# power.net
KiCad netlist of a schematic drawn in Altium Designer
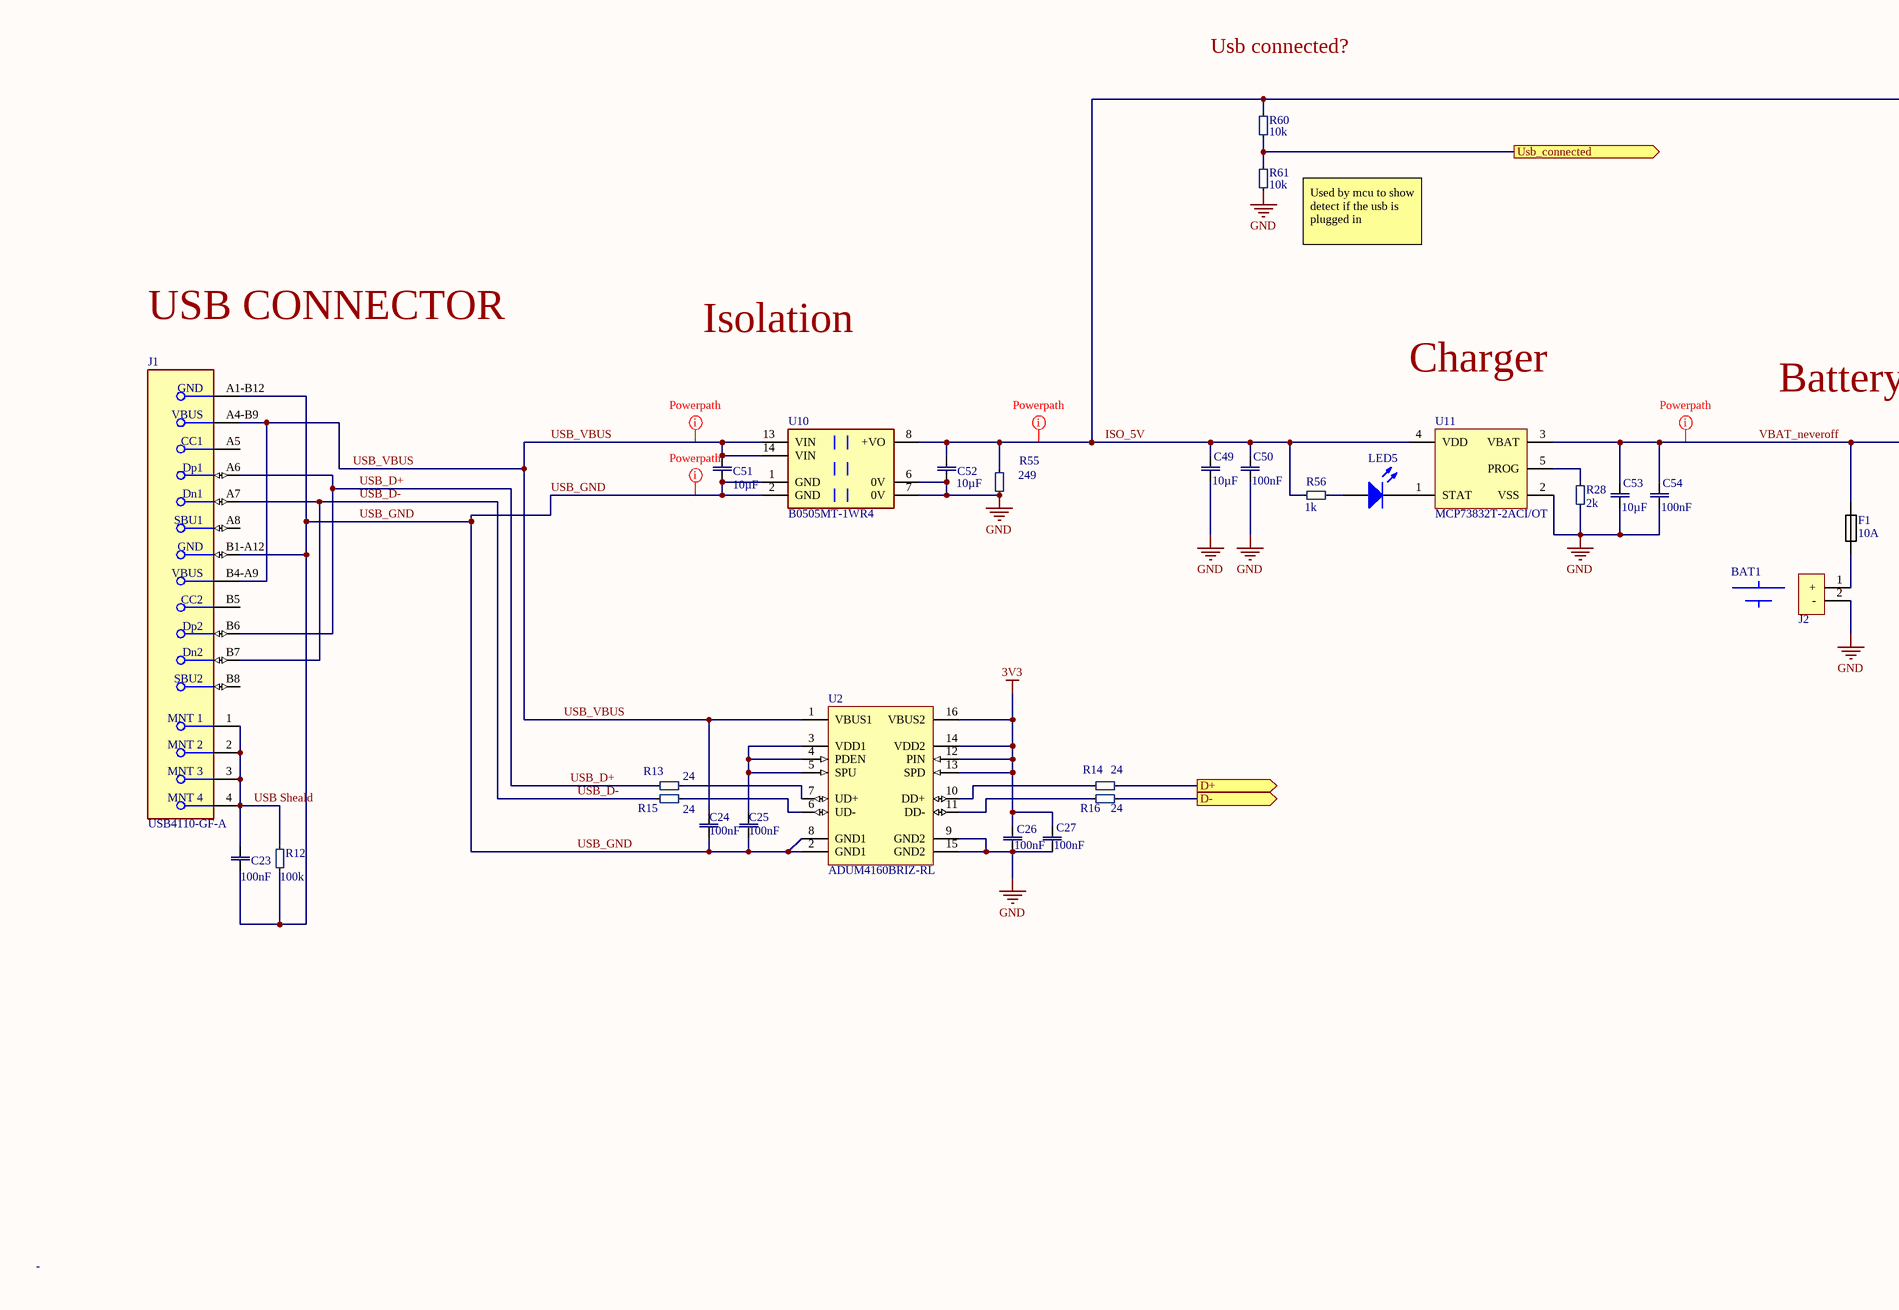
[diagram p0: power.SchDoc, left]
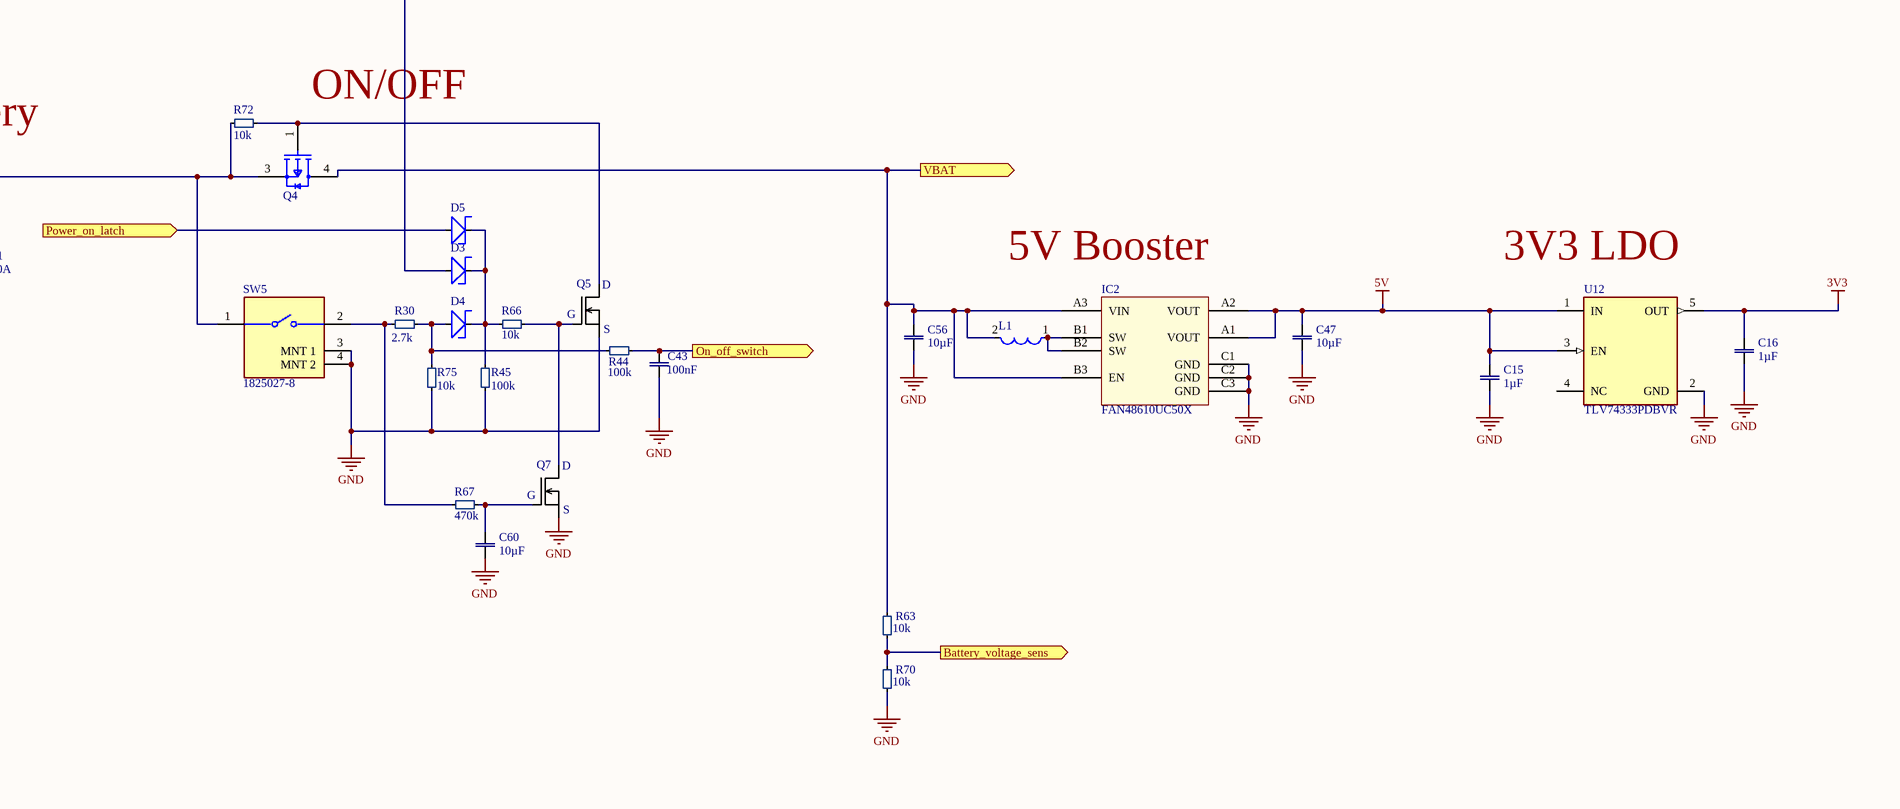
[diagram p1: power.SchDoc, right]

(export (version "E")
  (design (tool "Eeschema 10.0.6"))
  (components
    (comp (ref "BAT1")
      (value "THN803465AJ")
      (footprint "THN803465AJ-Footprint-1")
      (description "2500mAh 3.7V 1S 25C LiPO Battery JST plug for Drone RC Model Airplane Helicopter")
      (fields (field (name "VOLTAGE") "3.7V"))
      (libsource (lib "concord server") (part "battery"))
    )
    (comp (ref "C15")
      (value "CL21B105KBFNNNG")
      (footprint "CAP0805")
      (description "SAMSUNG ELECTRO-MECHANICS - CL21B105KBFNNNG - MLCC CAPACITORS")
      (fields
        (field (name "VOLTAGE") "50V")
        (field (name "CAPACITANCE") "1µF")
        (field (name "TOLERANCE") "10%")
      )
      (libsource (lib "concord server") (part "Capasitor_keramic_generic"))
    )
    (comp (ref "C16")
      (value "CL21B105KBFNNNG")
      (footprint "CAP0805")
      (description "SAMSUNG ELECTRO-MECHANICS - CL21B105KBFNNNG - MLCC CAPACITORS")
      (fields
        (field (name "VOLTAGE") "50V")
        (field (name "CAPACITANCE") "1µF")
        (field (name "TOLERANCE") "10%")
      )
      (libsource (lib "concord server") (part "Capasitor_keramic_generic"))
    )
    (comp (ref "C23")
      (value "GRM155R71H104ME14D")
      (footprint "cap0402")
      (description "0402 0.1 uF 50 V ±20% Tolerance X7R SMT Monolithic Ceramic Chip Capacitor")
      (fields
        (field (name "CAPACITANCE") "100nF")
        (field (name "TOLERANCE") "20%")
        (field (name "LCSC PART#") "C182412")
      )
      (libsource (lib "concord server") (part "Capasitor_keramic_generic"))
    )
    (comp (ref "C24")
      (value "GRM155R71H104ME14D")
      (footprint "cap0402")
      (description "0402 0.1 uF 50 V ±20% Tolerance X7R SMT Monolithic Ceramic Chip Capacitor")
      (fields
        (field (name "CAPACITANCE") "100nF")
        (field (name "TOLERANCE") "20%")
        (field (name "LCSC PART#") "C182412")
      )
      (libsource (lib "concord server") (part "Capasitor_keramic_generic"))
    )
    (comp (ref "C25")
      (value "GRM155R71H104ME14D")
      (footprint "cap0402")
      (description "0402 0.1 uF 50 V ±20% Tolerance X7R SMT Monolithic Ceramic Chip Capacitor")
      (fields
        (field (name "CAPACITANCE") "100nF")
        (field (name "TOLERANCE") "20%")
        (field (name "LCSC PART#") "C182412")
      )
      (libsource (lib "concord server") (part "Capasitor_keramic_generic"))
    )
    (comp (ref "C26")
      (value "GRM155R71H104ME14D")
      (footprint "cap0402")
      (description "0402 0.1 uF 50 V ±20% Tolerance X7R SMT Monolithic Ceramic Chip Capacitor")
      (fields
        (field (name "CAPACITANCE") "100nF")
        (field (name "TOLERANCE") "20%")
        (field (name "LCSC PART#") "C182412")
      )
      (libsource (lib "concord server") (part "Capasitor_keramic_generic"))
    )
    (comp (ref "C27")
      (value "GRM155R71H104ME14D")
      (footprint "cap0402")
      (description "0402 0.1 uF 50 V ±20% Tolerance X7R SMT Monolithic Ceramic Chip Capacitor")
      (fields
        (field (name "CAPACITANCE") "100nF")
        (field (name "TOLERANCE") "20%")
        (field (name "LCSC PART#") "C182412")
      )
      (libsource (lib "concord server") (part "Capasitor_keramic_generic"))
    )
    (comp (ref "C43")
      (value "GRM155R71H104ME14D")
      (footprint "cap0402")
      (description "0402 0.1 uF 50 V ±20% Tolerance X7R SMT Monolithic Ceramic Chip Capacitor")
      (fields
        (field (name "CAPACITANCE") "100nF")
        (field (name "TOLERANCE") "20%")
        (field (name "LCSC PART#") "C182412")
      )
      (libsource (lib "concord server") (part "Capasitor_keramic_generic"))
    )
    (comp (ref "C47")
      (value "CL31A106MBHNNNE")
      (footprint "Chip2PinSM127P600-8N")
      (description "CAP CER 10UF 50V X5R 1206")
      (fields
        (field (name "CAPACITANCE") "10µF")
        (field (name "TOLERANCE") "20%")
        (field (name "LCSC PART#") "C96600")
      )
      (libsource (lib "concord server") (part "Capasitor_keramic_generic"))
    )
    (comp (ref "C49")
      (value "CL31A106MBHNNNE")
      (footprint "Chip2PinSM127P600-8N")
      (description "CAP CER 10UF 50V X5R 1206")
      (fields
        (field (name "CAPACITANCE") "10µF")
        (field (name "TOLERANCE") "20%")
        (field (name "LCSC PART#") "C96600")
      )
      (libsource (lib "concord server") (part "Capasitor_keramic_generic"))
    )
    (comp (ref "C50")
      (value "GRM155R71H104ME14D")
      (footprint "cap0402")
      (description "0402 0.1 uF 50 V ±20% Tolerance X7R SMT Monolithic Ceramic Chip Capacitor")
      (fields
        (field (name "CAPACITANCE") "100nF")
        (field (name "TOLERANCE") "20%")
        (field (name "LCSC PART#") "C182412")
      )
      (libsource (lib "concord server") (part "Capasitor_keramic_generic"))
    )
    (comp (ref "C51")
      (value "CL31A106MBHNNNE")
      (footprint "Chip2PinSM127P600-8N")
      (description "CAP CER 10UF 50V X5R 1206")
      (fields
        (field (name "CAPACITANCE") "10µF")
        (field (name "TOLERANCE") "20%")
        (field (name "LCSC PART#") "C96600")
      )
      (libsource (lib "concord server") (part "Capasitor_keramic_generic"))
    )
    (comp (ref "C52")
      (value "CL31A106MBHNNNE")
      (footprint "Chip2PinSM127P600-8N")
      (description "CAP CER 10UF 50V X5R 1206")
      (fields
        (field (name "CAPACITANCE") "10µF")
        (field (name "TOLERANCE") "20%")
        (field (name "LCSC PART#") "C96600")
      )
      (libsource (lib "concord server") (part "Capasitor_keramic_generic"))
    )
    (comp (ref "C53")
      (value "CL31A106MBHNNNE")
      (footprint "Chip2PinSM127P600-8N")
      (description "CAP CER 10UF 50V X5R 1206")
      (fields
        (field (name "CAPACITANCE") "10µF")
        (field (name "TOLERANCE") "20%")
        (field (name "LCSC PART#") "C96600")
      )
      (libsource (lib "concord server") (part "Capasitor_keramic_generic"))
    )
    (comp (ref "C54")
      (value "GRM155R71H104ME14D")
      (footprint "cap0402")
      (description "0402 0.1 uF 50 V ±20% Tolerance X7R SMT Monolithic Ceramic Chip Capacitor")
      (fields
        (field (name "CAPACITANCE") "100nF")
        (field (name "TOLERANCE") "20%")
        (field (name "LCSC PART#") "C182412")
      )
      (libsource (lib "concord server") (part "Capasitor_keramic_generic"))
    )
    (comp (ref "C56")
      (value "CL31A106MBHNNNE")
      (footprint "Chip2PinSM127P600-8N")
      (description "CAP CER 10UF 50V X5R 1206")
      (fields
        (field (name "CAPACITANCE") "10µF")
        (field (name "TOLERANCE") "20%")
        (field (name "LCSC PART#") "C96600")
      )
      (libsource (lib "concord server") (part "Capasitor_keramic_generic"))
    )
    (comp (ref "C60")
      (value "CL31A106MBHNNNE")
      (footprint "Chip2PinSM127P600-8N")
      (description "CAP CER 10UF 50V X5R 1206")
      (fields
        (field (name "CAPACITANCE") "10µF")
        (field (name "TOLERANCE") "20%")
        (field (name "LCSC PART#") "C96600")
      )
      (libsource (lib "concord server") (part "Capasitor_keramic_generic"))
    )
    (comp (ref "D3")
      (value "BAS70_R1_00001")
      (footprint "SOT95P245X110-3N")
      (description "Diode Schottky 70 V 200mA Surface Mount SOT-23")
      (libsource (lib "concord server") (part "Schootkey diode"))
    )
    (comp (ref "D4")
      (value "BAS70_R1_00001")
      (footprint "SOT95P245X110-3N")
      (description "Diode Schottky 70 V 200mA Surface Mount SOT-23")
      (libsource (lib "concord server") (part "Schootkey diode"))
    )
    (comp (ref "D5")
      (value "BAS70_R1_00001")
      (footprint "SOT95P245X110-3N")
      (description "Diode Schottky 70 V 200mA Surface Mount SOT-23")
      (libsource (lib "concord server") (part "Schootkey diode"))
    )
    (comp (ref "F1")
      (value "0685H9100-01")
      (footprint "RESC3216X06N")
      (description "Fuse Chip Fast Acting 10A 125V SMD Solder Pad 1206 3.2 X 1.58 X 0.65mm Ceramic T/R Automotive")
      (fields (field (name "CURRENT RATING") "10A"))
      (libsource (lib "concord server") (part "0685H9100-01-Symbol-1"))
    )
    (comp (ref "IC2")
      (value "FAN48610UC50X")
      (footprint "BGA9C40P3X3_211X211X58")
      (description "2.5 MHz, 1 A, Fixed-Output Synchronous TinyBoost® Regulator")
      (fields (field (name "LCSC PART#") "C890712"))
      (libsource (lib "concord server") (part "FAN48610UC50X-Symbol-1"))
    )
    (comp (ref "J1")
      (value "USB4110-GF-A")
      (footprint "FP-USB4110-GF-A-MFG")
      (description "Conn Usb 2.0 Type-c R/a SMT")
      (libsource (lib "concord server") (part "e23f2b38bb3c3f98e683ebab9ede730"))
    )
    (comp (ref "J2")
      (value "1744048-2")
      (footprint "New footprint 1")
      (description "Conn Power HDR 2 POS 5.08mm Solder RA Thru-Hole 2 Terminal 1 Port Bag")
      (fields (field (name "LCSC PART#") "C590637"))
      (libsource (lib "concord server") (part "BU-P6883"))
    )
    (comp (ref "L1")
      (value "LQM21PNR47MC0D")
      (footprint "FP-LQM21PN_C0-IPC_C")
      (description "Inductor Power Chip Shielded Multi-Layer 0.47uH 20% 1MHz Ferrite 1.1A 0.15Ohm DCR 0805 T/R")
      (fields (field (name "LCSC PART#") "C341670"))
      (libsource (lib "concord server") (part "725321dda6339637d4d059423bc1c3c"))
    )
    (comp (ref "LED5")
      (value "150080BS75000")
      (footprint "0805_A")
      (description "SMD LED blue 3.5 V 0805, 150080BS75000, Würth Elektronik")
      (libsource (lib "concord server") (part "WE-LED_K1A2-2"))
    )
    (comp (ref "Q4")
      (value "RQ3C150BCTB")
      (footprint "RQ3C150BCTB-Footprint-1")
      (description "Trans Mosfet P-ch 20V 15A 8-PIN Hsmt Ep T/r")
      (fields (field (name "LCSC PART#") "C266247"))
      (libsource (lib "concord server") (part "pmos"))
    )
    (comp (ref "Q5")
      (value "SSM3K7002CFU,LF")
      (footprint "SSM3K7002CFU,LF-Footprint-1")
      (description "Trans MOSFET N-CH Si 60V 0.17A 3-Pin USM T/R")
      (fields (field (name "LCSC PART#") "C396059"))
      (libsource (lib "concord server") (part "nmos"))
    )
    (comp (ref "Q7")
      (value "SSM3K7002CFU,LF")
      (footprint "SSM3K7002CFU,LF-Footprint-1")
      (description "Trans MOSFET N-CH Si 60V 0.17A 3-Pin USM T/R")
      (fields (field (name "LCSC PART#") "C396059"))
      (libsource (lib "concord server") (part "nmos"))
    )
    (comp (ref "R12")
      (value "RC0402FR-07100KL")
      (footprint "SMD_0402(1005)_M")
      (description "Res General Purpose Thick Film 0402 100K Ohm 1% 1/16W ±100ppm/°C Molded SMD Paper T/R")
      (fields
        (field (name "RESISTANCE") "100k")
        (field (name "TOLERANCE") "1%")
        (field (name "LCSC PART#") "C60491")
      )
      (libsource (lib "concord server") (part "resistor_european"))
    )
    (comp (ref "R13")
      (value "RC0402FR-0724RL")
      (footprint "RESC0402(1005)_N")
      (description "Thick Film Resistors 24 OHM 1%")
      (fields
        (field (name "RESISTANCE") "24")
        (field (name "TOLERANCE") "1%")
        (field (name "LCSC PART#") "C274890")
      )
      (libsource (lib "concord server") (part "resistor_european"))
    )
    (comp (ref "R14")
      (value "RC0402FR-0724RL")
      (footprint "RESC0402(1005)_N")
      (description "Thick Film Resistors 24 OHM 1%")
      (fields
        (field (name "RESISTANCE") "24")
        (field (name "TOLERANCE") "1%")
        (field (name "LCSC PART#") "C274890")
      )
      (libsource (lib "concord server") (part "resistor_european"))
    )
    (comp (ref "R15")
      (value "RC0402FR-0724RL")
      (footprint "RESC0402(1005)_N")
      (description "Thick Film Resistors 24 OHM 1%")
      (fields
        (field (name "RESISTANCE") "24")
        (field (name "TOLERANCE") "1%")
        (field (name "LCSC PART#") "C274890")
      )
      (libsource (lib "concord server") (part "resistor_european"))
    )
    (comp (ref "R16")
      (value "RC0402FR-0724RL")
      (footprint "RESC0402(1005)_N")
      (description "Thick Film Resistors 24 OHM 1%")
      (fields
        (field (name "RESISTANCE") "24")
        (field (name "TOLERANCE") "1%")
        (field (name "LCSC PART#") "C274890")
      )
      (libsource (lib "concord server") (part "resistor_european"))
    )
    (comp (ref "R28")
      (value "RC0402FR-072KL")
      (footprint "RESC1005X40X25NL05T10")
      (description "Res General Purpose Thick Film 0402 2K Ohm 1% 1/16W ±100ppm/°C Molded SMD Paper T/R")
      (fields
        (field (name "RESISTANCE") "2k")
        (field (name "TOLERANCE") "1%")
        (field (name "LCSC PART#") "C138017")
      )
      (libsource (lib "concord server") (part "resistor_european"))
    )
    (comp (ref "R30")
      (value "RC0402FR-072K7L")
      (footprint "RESC1005X40X25NL05T10")
      (description "Res General Purpose Thick Film 0402 2.7k Ohm 1% 1/16W ±100ppm/°C Molded Paper T/R")
      (fields
        (field (name "RESISTANCE") "2.7k")
        (field (name "TOLERANCE") "1%")
        (field (name "LCSC PART#") "C138017")
      )
      (libsource (lib "concord server") (part "resistor_european"))
    )
    (comp (ref "R44")
      (value "RC0402FR-07100KL")
      (footprint "SMD_0402(1005)_M")
      (description "Res General Purpose Thick Film 0402 100K Ohm 1% 1/16W ±100ppm/°C Molded SMD Paper T/R")
      (fields
        (field (name "RESISTANCE") "100k")
        (field (name "TOLERANCE") "1%")
        (field (name "LCSC PART#") "C60491")
      )
      (libsource (lib "concord server") (part "resistor_european"))
    )
    (comp (ref "R45")
      (value "RC0402FR-07100KL")
      (footprint "SMD_0402(1005)_M")
      (description "Res General Purpose Thick Film 0402 100K Ohm 1% 1/16W ±100ppm/°C Molded SMD Paper T/R")
      (fields
        (field (name "RESISTANCE") "100k")
        (field (name "TOLERANCE") "1%")
        (field (name "LCSC PART#") "C60491")
      )
      (libsource (lib "concord server") (part "resistor_european"))
    )
    (comp (ref "R55")
      (value "RC0402FR-07249RL")
      (footprint "SMD_0402(1005)_M")
      (description "Res Thick Film 0402 249 Ohm 1% 1/16W ±100ppm/°C Molded SMD Paper T/R")
      (fields
        (field (name "RESISTANCE") "249")
        (field (name "TOLERANCE") "1%")
        (field (name "LCSC PART#") "C185439")
      )
      (libsource (lib "concord server") (part "resistor_european"))
    )
    (comp (ref "R56")
      (value "RC0402FR-071KL")
      (footprint "SMD_0402(1005)_M")
      (description "Surface Mount Chip Resistor, Thick Film, RC Series, 1 kohm, 62.5 mW, 1%, 50 V, 0402 [1005 Metric]")
      (fields
        (field (name "RESISTANCE") "1k")
        (field (name "TOLERANCE") "1%")
        (field (name "LCSC PART#") "C2935237")
      )
      (libsource (lib "concord server") (part "resistor_european"))
    )
    (comp (ref "R60")
      (value "RC0402FR-0710KL")
      (footprint "SMD_0402(1005)_M")
      (description "Surface Mount Thick Film Resistor, Rc Series, 10 Kohm, 62.5 Mw, - 1%, 50 V, 0402 [1005 Metric]")
      (fields
        (field (name "RESISTANCE") "10k")
        (field (name "TOLERANCE") "1%")
        (field (name "LCSC PART#") "C60490")
      )
      (libsource (lib "concord server") (part "resistor_european"))
    )
    (comp (ref "R61")
      (value "RC0402FR-0710KL")
      (footprint "SMD_0402(1005)_M")
      (description "Surface Mount Thick Film Resistor, Rc Series, 10 Kohm, 62.5 Mw, - 1%, 50 V, 0402 [1005 Metric]")
      (fields
        (field (name "RESISTANCE") "10k")
        (field (name "TOLERANCE") "1%")
        (field (name "LCSC PART#") "C60490")
      )
      (libsource (lib "concord server") (part "resistor_european"))
    )
    (comp (ref "R63")
      (value "RC0402FR-0710KL")
      (footprint "SMD_0402(1005)_M")
      (description "Surface Mount Thick Film Resistor, Rc Series, 10 Kohm, 62.5 Mw, - 1%, 50 V, 0402 [1005 Metric]")
      (fields
        (field (name "RESISTANCE") "10k")
        (field (name "TOLERANCE") "1%")
        (field (name "LCSC PART#") "C60490")
      )
      (libsource (lib "concord server") (part "resistor_european"))
    )
    (comp (ref "R66")
      (value "RC0402FR-0710KL")
      (footprint "SMD_0402(1005)_M")
      (description "Surface Mount Thick Film Resistor, Rc Series, 10 Kohm, 62.5 Mw, - 1%, 50 V, 0402 [1005 Metric]")
      (fields
        (field (name "RESISTANCE") "10k")
        (field (name "TOLERANCE") "1%")
        (field (name "LCSC PART#") "C60490")
      )
      (libsource (lib "concord server") (part "resistor_european"))
    )
    (comp (ref "R67")
      (value "RC0402FR-07470KL")
      (footprint "SMD_0402(1005)_M")
      (description "Res Thick Film 0402 470K Ohm 1% 1/16W +/-100ppm/ßC Molded SMD Paper T/R")
      (fields
        (field (name "RESISTANCE") "470k")
        (field (name "TOLERANCE") "1%")
        (field (name "LCSC PART#") "C60491")
      )
      (libsource (lib "concord server") (part "resistor_european"))
    )
    (comp (ref "R70")
      (value "RC0402FR-0710KL")
      (footprint "SMD_0402(1005)_M")
      (description "Surface Mount Thick Film Resistor, Rc Series, 10 Kohm, 62.5 Mw, - 1%, 50 V, 0402 [1005 Metric]")
      (fields
        (field (name "RESISTANCE") "10k")
        (field (name "TOLERANCE") "1%")
        (field (name "LCSC PART#") "C60490")
      )
      (libsource (lib "concord server") (part "resistor_european"))
    )
    (comp (ref "R72")
      (value "RC0402FR-0710KL")
      (footprint "SMD_0402(1005)_M")
      (description "Surface Mount Thick Film Resistor, Rc Series, 10 Kohm, 62.5 Mw, - 1%, 50 V, 0402 [1005 Metric]")
      (fields
        (field (name "RESISTANCE") "10k")
        (field (name "TOLERANCE") "1%")
        (field (name "LCSC PART#") "C60490")
      )
      (libsource (lib "concord server") (part "resistor_european"))
    )
    (comp (ref "R75")
      (value "RC0402FR-0710KL")
      (footprint "SMD_0402(1005)_M")
      (description "Surface Mount Thick Film Resistor, Rc Series, 10 Kohm, 62.5 Mw, - 1%, 50 V, 0402 [1005 Metric]")
      (fields
        (field (name "RESISTANCE") "10k")
        (field (name "TOLERANCE") "1%")
        (field (name "LCSC PART#") "C60490")
      )
      (libsource (lib "concord server") (part "resistor_european"))
    )
    (comp (ref "SW5")
      (value "1825027-8")
      (footprint "FP-1825027-8-MFG")
      (description "Switch Tactile OFF (ON) SPST Round Button PC Pins 0.05A 24VDC 1.57N Thru-Hole Loose Piece")
      (fields (field (name "LCSC PART#") "C266196"))
      (libsource (lib "concord server") (part "710c863c6dfdf6196cc88dcf85d5a08"))
    )
    (comp (ref "U2")
      (value "ADUM4160BRIZ-RL")
      (footprint "ADI-RI-16-1_N")
      (description "Digital Isolator CMOS 4-CH 12Mbps 16-Pin SOIC T/R")
      (fields (field (name "LCSC PART#") "C660968"))
      (libsource (lib "concord server") (part "ADI-ADUM4160-16"))
    )
    (comp (ref "U10")
      (value "B0505MT-1WR4")
      (footprint "FP-B0505MT-1WR4-MFG")
      (description "DC DC Converter 5V 1W")
      (fields (field (name "LCSC PART#") "C919693"))
      (libsource (lib "concord server") (part "6a7141d3c8d3c77bdd270da68c65698"))
    )
    (comp (ref "U11")
      (value "MCP73832T-2ACI/OT")
      (footprint "SOT-23-OT5_M")
      (fields (field (name "LCSC PART#") "C38066"))
      (libsource (lib "concord server") (part "PM-BM-MCP73832-SOT5"))
    )
    (comp (ref "U12")
      (value "TLV74333PDBVR")
      (footprint "FP-DBV0005A-IPC_A")
      (description "300mA Low-Dropout (LDO) Regulator 5-SOT-23 -40 to 125")
      (fields (field (name "LCSC PART#") "C408972"))
      (libsource (lib "concord server") (part "3a8dd6e68b3b0d4ea301bae8a2f3989"))
    )
  )
  (nets
    (net (code "1") (name "/Battery_voltage_sens") (class "Default")
      (node (ref "R63") (pin "1") (pinfunction "1_1") (pintype "passive"))
      (node (ref "R70") (pin "2") (pinfunction "2_2") (pintype "passive"))
    )
    (net (code "2") (name "/D+") (class "Default")
      (node (ref "R14") (pin "2") (pinfunction "2_2") (pintype "passive"))
    )
    (net (code "3") (name "/D-") (class "Default")
      (node (ref "R16") (pin "2") (pinfunction "2_2") (pintype "passive"))
    )
    (net (code "4") (name "/ISO_5V") (class "Default")
      (node (ref "C49") (pin "2") (pinfunction "2_2") (pintype "passive"))
      (node (ref "C50") (pin "2") (pinfunction "2_2") (pintype "passive"))
      (node (ref "C52") (pin "2") (pinfunction "2_2") (pintype "passive"))
      (node (ref "D3") (pin "1") (pinfunction "A_1") (pintype "passive"))
      (node (ref "R55") (pin "2") (pinfunction "2_2") (pintype "passive"))
      (node (ref "R56") (pin "2") (pinfunction "2_2") (pintype "passive"))
      (node (ref "R60") (pin "2") (pinfunction "2_2") (pintype "passive"))
      (node (ref "U10") (pin "8") (pinfunction "+VO_8") (pintype "power_in"))
      (node (ref "U11") (pin "4") (pinfunction "VDD_4") (pintype "power_in"))
    )
    (net (code "5") (name "/On_off_switch") (class "Default")
      (node (ref "C43") (pin "2") (pinfunction "2_2") (pintype "passive"))
      (node (ref "R44") (pin "1") (pinfunction "1_1") (pintype "passive"))
    )
    (net (code "6") (name "/Power_on_latch") (class "Default")
      (node (ref "D5") (pin "1") (pinfunction "A_1") (pintype "passive"))
    )
    (net (code "7") (name "/USB Sheald") (class "Default")
      (node (ref "C23") (pin "2") (pinfunction "2_2") (pintype "passive"))
      (node (ref "J1") (pin "1") (pinfunction "MNT_1_1") (pintype "passive"))
      (node (ref "J1") (pin "2") (pinfunction "MNT_2_2") (pintype "passive"))
      (node (ref "J1") (pin "3") (pinfunction "MNT_3_3") (pintype "passive"))
      (node (ref "J1") (pin "4") (pinfunction "MNT_4_4") (pintype "passive"))
      (node (ref "R12") (pin "2") (pinfunction "2_2") (pintype "passive"))
    )
    (net (code "8") (name "/USB_D+") (class "Default")
      (node (ref "J1") (pin "A6") (pinfunction "Dp1_A6") (pintype "bidirectional"))
      (node (ref "J1") (pin "B6") (pinfunction "Dp2_B6") (pintype "bidirectional"))
      (node (ref "R13") (pin "1") (pinfunction "1_1") (pintype "passive"))
    )
    (net (code "9") (name "/USB_D-") (class "Default")
      (node (ref "J1") (pin "A7") (pinfunction "Dn1_A7") (pintype "bidirectional"))
      (node (ref "J1") (pin "B7") (pinfunction "Dn2_B7") (pintype "bidirectional"))
      (node (ref "R15") (pin "1") (pinfunction "1_1") (pintype "passive"))
    )
    (net (code "10") (name "/USB_GND") (class "Default")
      (node (ref "C23") (pin "1") (pinfunction "1_1") (pintype "passive"))
      (node (ref "C24") (pin "1") (pinfunction "1_1") (pintype "passive"))
      (node (ref "C25") (pin "2") (pinfunction "2_2") (pintype "passive"))
      (node (ref "C51") (pin "1") (pinfunction "1_1") (pintype "passive"))
      (node (ref "J1") (pin "A1-B12") (pinfunction "GND_A1-B12") (pintype "passive"))
      (node (ref "J1") (pin "B1-A12") (pinfunction "GND_B1-A12") (pintype "bidirectional"))
      (node (ref "R12") (pin "1") (pinfunction "1_1") (pintype "passive"))
      (node (ref "U10") (pin "1") (pinfunction "GND_1") (pintype "power_in"))
      (node (ref "U10") (pin "2") (pinfunction "GND_2") (pintype "power_in"))
      (node (ref "U2") (pin "2") (pinfunction "GND1_2") (pintype "power_in"))
      (node (ref "U2") (pin "8") (pinfunction "GND1_8") (pintype "power_in"))
    )
    (net (code "11") (name "/USB_VBUS") (class "Default")
      (node (ref "C24") (pin "2") (pinfunction "2_2") (pintype "passive"))
      (node (ref "C51") (pin "2") (pinfunction "2_2") (pintype "passive"))
      (node (ref "J1") (pin "A4-B9") (pinfunction "VBUS_A4-B9") (pintype "power_in"))
      (node (ref "J1") (pin "B4-A9") (pinfunction "VBUS_B4-A9") (pintype "power_in"))
      (node (ref "U10") (pin "13") (pinfunction "VIN_13") (pintype "power_in"))
      (node (ref "U10") (pin "14") (pinfunction "VIN_14") (pintype "power_in"))
      (node (ref "U2") (pin "1") (pinfunction "VBUS1_1") (pintype "power_in"))
    )
    (net (code "12") (name "/Usb_connected") (class "Default")
      (node (ref "R60") (pin "1") (pinfunction "1_1") (pintype "passive"))
      (node (ref "R61") (pin "2") (pinfunction "2_2") (pintype "passive"))
    )
    (net (code "13") (name "/VBAT") (class "Default")
      (node (ref "C56") (pin "2") (pinfunction "2_2") (pintype "passive"))
      (node (ref "IC2") (pin "A3") (pinfunction "VIN_A3") (pintype "passive"))
      (node (ref "IC2") (pin "B3") (pinfunction "EN_B3") (pintype "passive"))
      (node (ref "L1") (pin "2") (pinfunction "2_2") (pintype "passive"))
      (node (ref "Q4") (pin "4") (pinfunction "D_4") (pintype "passive"))
      (node (ref "R63") (pin "2") (pinfunction "2_2") (pintype "passive"))
    )
    (net (code "14") (name "/VBAT_neveroff") (class "Default")
      (node (ref "C53") (pin "2") (pinfunction "2_2") (pintype "passive"))
      (node (ref "C54") (pin "2") (pinfunction "2_2") (pintype "passive"))
      (node (ref "F1") (pin "1") (pinfunction "1_1") (pintype "passive"))
      (node (ref "Q4") (pin "3") (pinfunction "S_3") (pintype "passive"))
      (node (ref "R72") (pin "1") (pinfunction "1_1") (pintype "passive"))
      (node (ref "SW5") (pin "1") (pinfunction "1_1") (pintype "passive"))
      (node (ref "U11") (pin "3") (pinfunction "VBAT_3") (pintype "power_in"))
    )
    (net (code "15") (name "3V3") (class "Default")
      (node (ref "C16") (pin "2") (pinfunction "2_2") (pintype "passive"))
      (node (ref "C26") (pin "1") (pinfunction "1_1") (pintype "passive"))
      (node (ref "C27") (pin "1") (pinfunction "1_1") (pintype "passive"))
      (node (ref "U12") (pin "5") (pinfunction "OUT_5") (pintype "output"))
      (node (ref "U2") (pin "12") (pinfunction "PIN_12") (pintype "input"))
      (node (ref "U2") (pin "13") (pinfunction "SPD_13") (pintype "input"))
      (node (ref "U2") (pin "14") (pinfunction "VDD2_14") (pintype "power_in"))
      (node (ref "U2") (pin "16") (pinfunction "VBUS2_16") (pintype "power_in"))
    )
    (net (code "16") (name "5V") (class "Default")
      (node (ref "C15") (pin "2") (pinfunction "2_2") (pintype "passive"))
      (node (ref "C47") (pin "2") (pinfunction "2_2") (pintype "passive"))
      (node (ref "IC2") (pin "A1") (pinfunction "VOUT_A1") (pintype "passive"))
      (node (ref "IC2") (pin "A2") (pinfunction "VOUT_A2") (pintype "passive"))
      (node (ref "U12") (pin "1") (pinfunction "IN_1") (pintype "power_in"))
      (node (ref "U12") (pin "3") (pinfunction "EN_3") (pintype "input"))
    )
    (net (code "17") (name "GND") (class "Default")
      (node (ref "C15") (pin "1") (pinfunction "1_1") (pintype "passive"))
      (node (ref "C16") (pin "1") (pinfunction "1_1") (pintype "passive"))
      (node (ref "C26") (pin "2") (pinfunction "2_2") (pintype "passive"))
      (node (ref "C27") (pin "2") (pinfunction "2_2") (pintype "passive"))
      (node (ref "C43") (pin "1") (pinfunction "1_1") (pintype "passive"))
      (node (ref "C47") (pin "1") (pinfunction "1_1") (pintype "passive"))
      (node (ref "C49") (pin "1") (pinfunction "1_1") (pintype "passive"))
      (node (ref "C50") (pin "1") (pinfunction "1_1") (pintype "passive"))
      (node (ref "C52") (pin "1") (pinfunction "1_1") (pintype "passive"))
      (node (ref "C53") (pin "1") (pinfunction "1_1") (pintype "passive"))
      (node (ref "C54") (pin "1") (pinfunction "1_1") (pintype "passive"))
      (node (ref "C56") (pin "1") (pinfunction "1_1") (pintype "passive"))
      (node (ref "C60") (pin "1") (pinfunction "1_1") (pintype "passive"))
      (node (ref "IC2") (pin "C1") (pinfunction "GND_C1") (pintype "passive"))
      (node (ref "IC2") (pin "C2") (pinfunction "GND_C2") (pintype "passive"))
      (node (ref "IC2") (pin "C3") (pinfunction "GND_C3") (pintype "passive"))
      (node (ref "J2") (pin "2") (pinfunction "-_2") (pintype "passive"))
      (node (ref "Q5") (pin "2") (pinfunction "D_2") (pintype "passive"))
      (node (ref "Q7") (pin "2") (pinfunction "D_2") (pintype "passive"))
      (node (ref "R28") (pin "1") (pinfunction "1_1") (pintype "passive"))
      (node (ref "R45") (pin "2") (pinfunction "2_2") (pintype "passive"))
      (node (ref "R55") (pin "1") (pinfunction "1_1") (pintype "passive"))
      (node (ref "R61") (pin "1") (pinfunction "1_1") (pintype "passive"))
      (node (ref "R70") (pin "1") (pinfunction "1_1") (pintype "passive"))
      (node (ref "R75") (pin "1") (pinfunction "1_1") (pintype "passive"))
      (node (ref "SW5") (pin "3") (pinfunction "MNT_1_3") (pintype "passive"))
      (node (ref "SW5") (pin "4") (pinfunction "MNT_2_4") (pintype "passive"))
      (node (ref "U10") (pin "6") (pinfunction "0V_6") (pintype "power_in"))
      (node (ref "U10") (pin "7") (pinfunction "0V_7") (pintype "power_in"))
      (node (ref "U11") (pin "2") (pinfunction "VSS_2") (pintype "power_in"))
      (node (ref "U12") (pin "2") (pinfunction "GND_2") (pintype "power_in"))
      (node (ref "U2") (pin "15") (pinfunction "GND2_15") (pintype "power_in"))
      (node (ref "U2") (pin "9") (pinfunction "GND2_9") (pintype "power_in"))
    )
    (net (code "18") (name "Net-(D3-K)") (class "Default")
      (node (ref "D3") (pin "2") (pinfunction "K_2") (pintype "passive"))
      (node (ref "D4") (pin "2") (pinfunction "K_2") (pintype "passive"))
      (node (ref "D5") (pin "2") (pinfunction "K_2") (pintype "passive"))
      (node (ref "R45") (pin "1") (pinfunction "1_1") (pintype "passive"))
      (node (ref "R66") (pin "2") (pinfunction "2_2") (pintype "passive"))
    )
    (net (code "19") (name "Net-(D4-A)") (class "Default")
      (node (ref "D4") (pin "1") (pinfunction "A_1") (pintype "passive"))
      (node (ref "R30") (pin "2") (pinfunction "2_2") (pintype "passive"))
      (node (ref "R44") (pin "2") (pinfunction "2_2") (pintype "passive"))
      (node (ref "R75") (pin "2") (pinfunction "2_2") (pintype "passive"))
    )
    (net (code "20") (name "Net-(IC2-SW-PadB1)") (class "Default")
      (node (ref "IC2") (pin "B1") (pinfunction "SW_B1") (pintype "passive"))
      (node (ref "IC2") (pin "B2") (pinfunction "SW_B2") (pintype "passive"))
      (node (ref "L1") (pin "1") (pinfunction "1_1") (pintype "passive"))
    )
    (net (code "21") (name "Net-(J2-+)") (class "Default")
      (node (ref "F1") (pin "2") (pinfunction "2_2") (pintype "passive"))
      (node (ref "J2") (pin "1") (pinfunction "+_1") (pintype "passive"))
    )
    (net (code "22") (name "Net-(LED5-A)") (class "Default")
      (node (ref "LED5") (pin "2") (pinfunction "A_2") (pintype "passive"))
      (node (ref "R56") (pin "1") (pinfunction "1_1") (pintype "passive"))
    )
    (net (code "23") (name "Net-(LED5-K)") (class "Default")
      (node (ref "LED5") (pin "1") (pinfunction "K_1") (pintype "passive"))
      (node (ref "U11") (pin "1") (pinfunction "STAT_1") (pintype "open_collector"))
    )
    (net (code "24") (name "Net-(Q4-G)") (class "Default")
      (node (ref "Q4") (pin "1") (pinfunction "G_1") (pintype "passive"))
      (node (ref "Q5") (pin "3") (pinfunction "S_3") (pintype "passive"))
      (node (ref "R72") (pin "2") (pinfunction "2_2") (pintype "passive"))
    )
    (net (code "25") (name "Net-(Q5-G)") (class "Default")
      (node (ref "Q5") (pin "1") (pinfunction "G_1") (pintype "passive"))
      (node (ref "Q7") (pin "3") (pinfunction "S_3") (pintype "passive"))
      (node (ref "R66") (pin "1") (pinfunction "1_1") (pintype "passive"))
    )
    (net (code "26") (name "Net-(Q7-G)") (class "Default")
      (node (ref "C60") (pin "2") (pinfunction "2_2") (pintype "passive"))
      (node (ref "Q7") (pin "1") (pinfunction "G_1") (pintype "passive"))
      (node (ref "R67") (pin "2") (pinfunction "2_2") (pintype "passive"))
    )
    (net (code "27") (name "Net-(R30-Pad1)") (class "Default")
      (node (ref "R30") (pin "1") (pinfunction "1_1") (pintype "passive"))
      (node (ref "R67") (pin "1") (pinfunction "1_1") (pintype "passive"))
      (node (ref "SW5") (pin "2") (pinfunction "2_2") (pintype "passive"))
    )
    (net (code "28") (name "Net-(U2-DD+)") (class "Default")
      (node (ref "R14") (pin "1") (pinfunction "1_1") (pintype "passive"))
      (node (ref "U2") (pin "10") (pinfunction "DD+_10") (pintype "bidirectional"))
    )
    (net (code "29") (name "Net-(U2-DD-)") (class "Default")
      (node (ref "R16") (pin "1") (pinfunction "1_1") (pintype "passive"))
      (node (ref "U2") (pin "11") (pinfunction "DD-_11") (pintype "bidirectional"))
    )
    (net (code "30") (name "Net-(U2-PDEN)") (class "Default")
      (node (ref "C25") (pin "1") (pinfunction "1_1") (pintype "passive"))
      (node (ref "U2") (pin "3") (pinfunction "VDD1_3") (pintype "power_in"))
      (node (ref "U2") (pin "4") (pinfunction "PDEN_4") (pintype "input"))
      (node (ref "U2") (pin "5") (pinfunction "SPU_5") (pintype "input"))
    )
    (net (code "31") (name "Net-(U2-UD+)") (class "Default")
      (node (ref "R13") (pin "2") (pinfunction "2_2") (pintype "passive"))
      (node (ref "U2") (pin "7") (pinfunction "UD+_7") (pintype "bidirectional"))
    )
    (net (code "32") (name "Net-(U2-UD-)") (class "Default")
      (node (ref "R15") (pin "2") (pinfunction "2_2") (pintype "passive"))
      (node (ref "U2") (pin "6") (pinfunction "UD-_6") (pintype "bidirectional"))
    )
    (net (code "33") (name "Net-(U11-PROG)") (class "Default")
      (node (ref "R28") (pin "2") (pinfunction "2_2") (pintype "passive"))
      (node (ref "U11") (pin "5") (pinfunction "PROG_5") (pintype "passive"))
    )
    (net (code "34") (name "unconnected-(J1-CC1-PadA5)") (class "Default")
      (node (ref "J1") (pin "A5") (pinfunction "CC1_A5") (pintype "power_in"))
    )
    (net (code "35") (name "unconnected-(J1-CC2-PadB5)") (class "Default")
      (node (ref "J1") (pin "B5") (pinfunction "CC2_B5") (pintype "power_in"))
    )
    (net (code "36") (name "unconnected-(J1-SBU1-PadA8)") (class "Default")
      (node (ref "J1") (pin "A8") (pinfunction "SBU1_A8") (pintype "bidirectional"))
    )
    (net (code "37") (name "unconnected-(J1-SBU2-PadB8)") (class "Default")
      (node (ref "J1") (pin "B8") (pinfunction "SBU2_B8") (pintype "bidirectional"))
    )
    (net (code "38") (name "unconnected-(U12-NC-Pad4)") (class "Default")
      (node (ref "U12") (pin "4") (pinfunction "NC_4") (pintype "passive"))
    )
  )
)
